# Thinkpad380ED.net
KiCad netlist of a schematic drawn in EAGLE
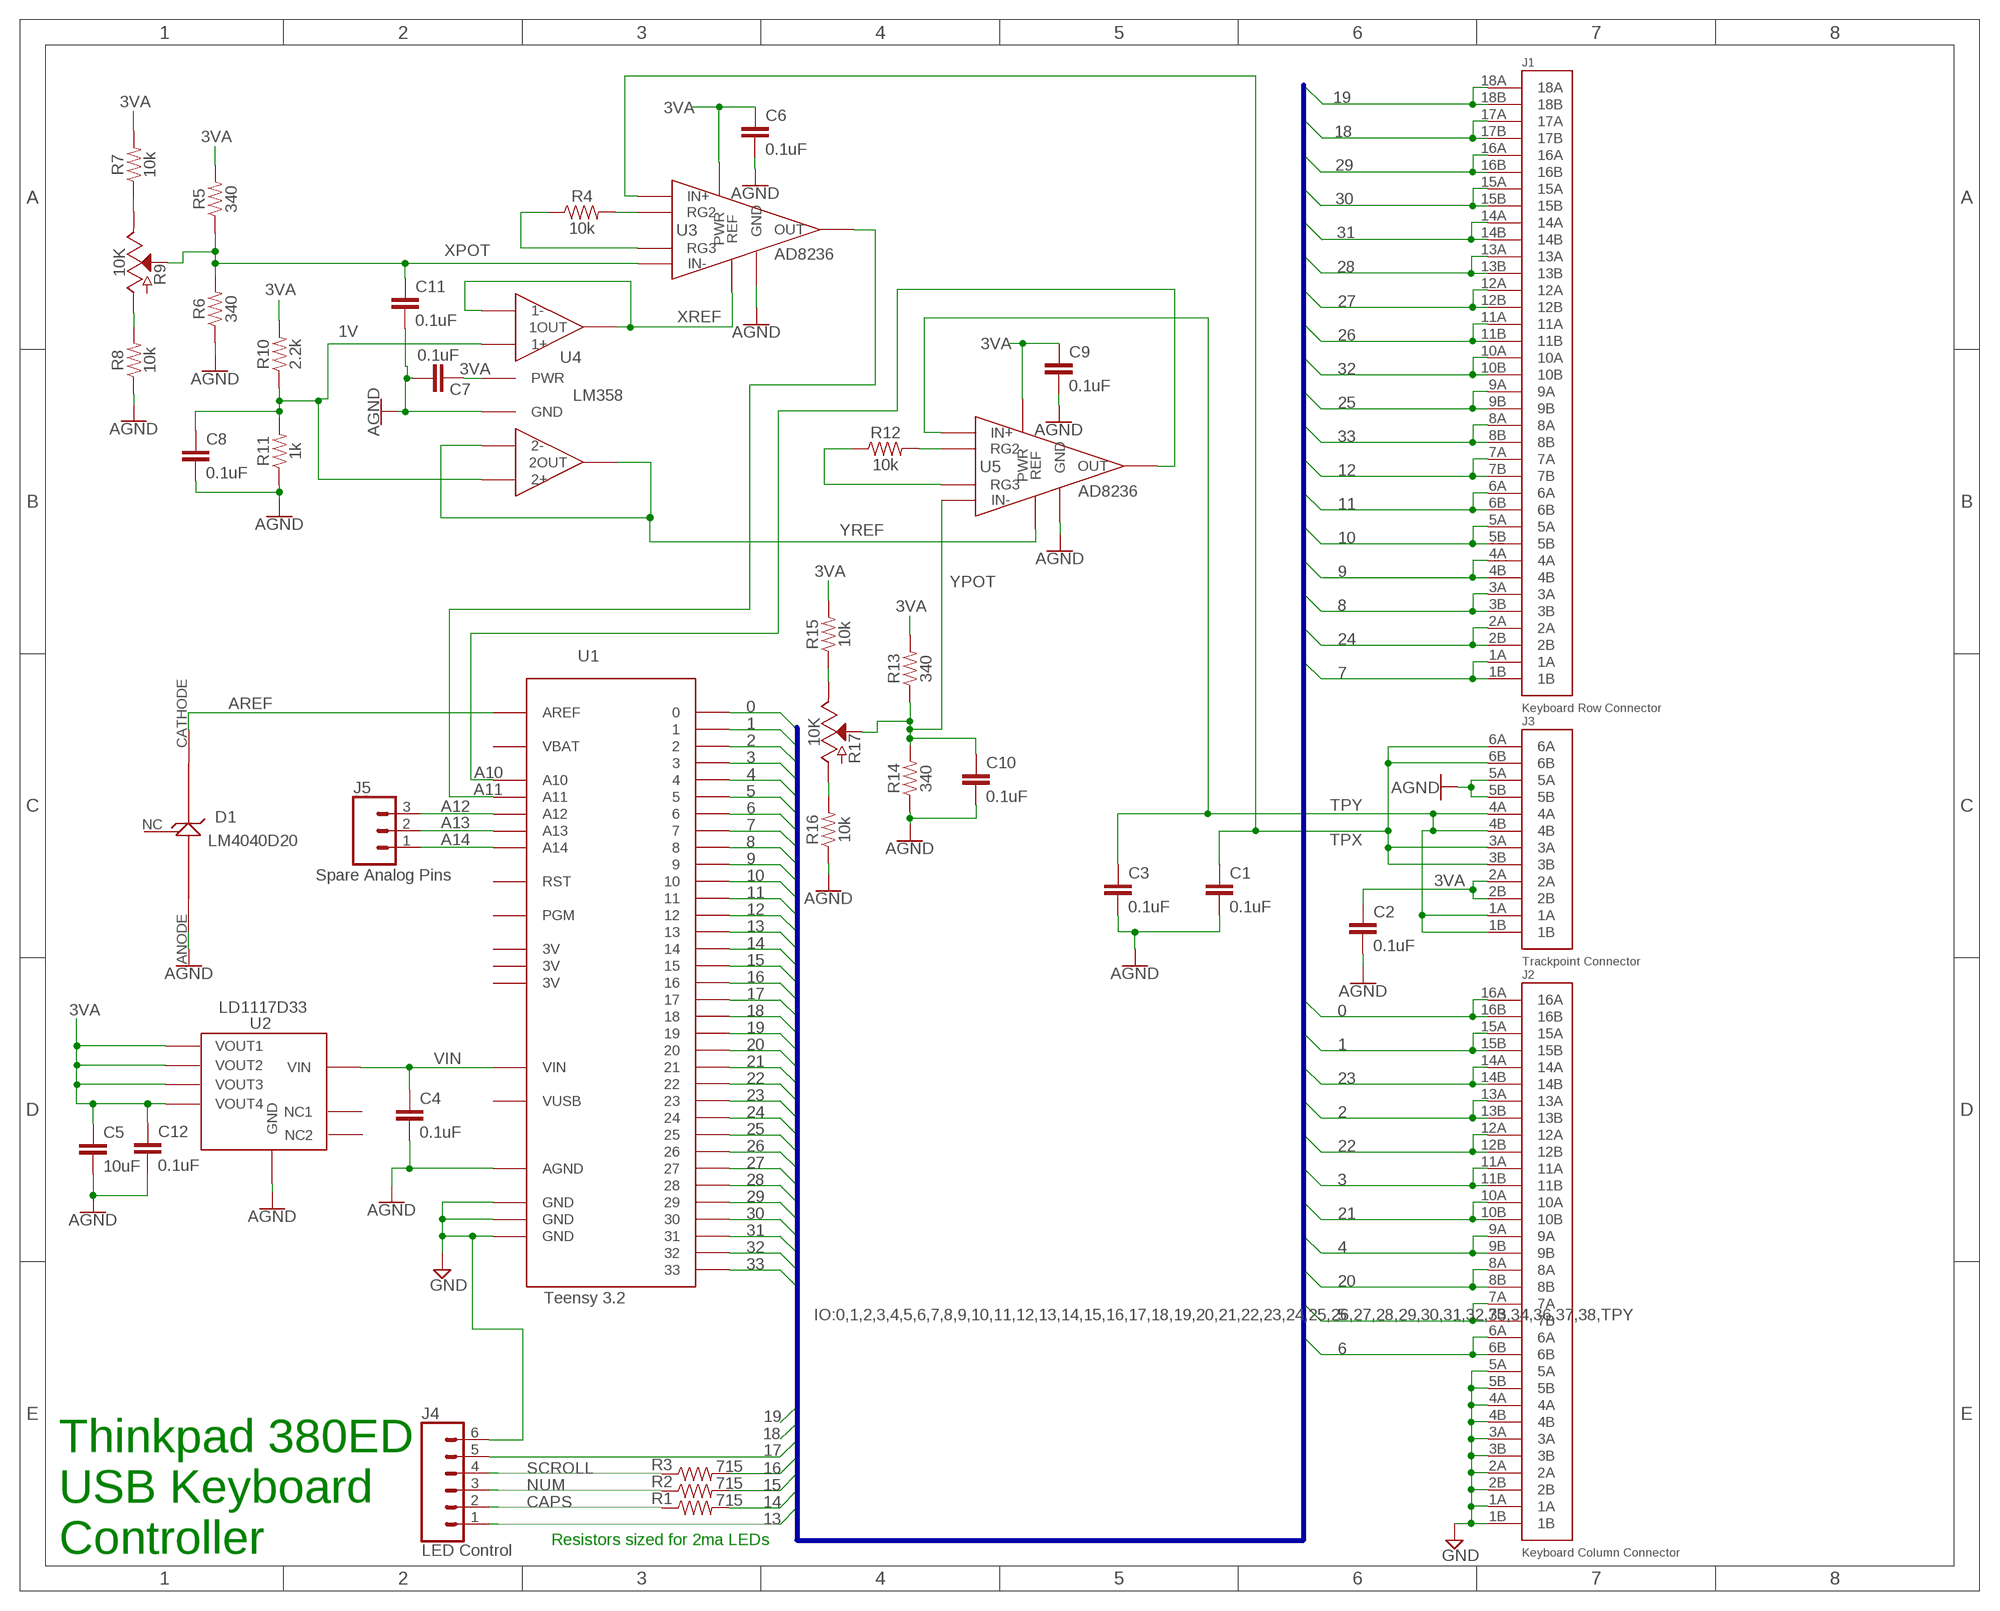
[diagram p0: schematic, sheet 1]

(export (version "E")
  (design (tool "Eeschema 10.0.6"))
  (components
    (comp (ref "C1")
      (value "0.1uF")
      (footprint "eagle-import:0603")
      (libsource (lib "eagle-import") (part "0.1UF-0603-25V-(+80/-20%)"))
    )
    (comp (ref "C2")
      (value "0.1uF")
      (footprint "eagle-import:0603")
      (libsource (lib "eagle-import") (part "0.1UF-0603-25V-(+80/-20%)"))
    )
    (comp (ref "C3")
      (value "0.1uF")
      (footprint "eagle-import:0603")
      (libsource (lib "eagle-import") (part "0.1UF-0603-25V-(+80/-20%)"))
    )
    (comp (ref "C4")
      (value "0.1uF")
      (footprint "eagle-import:0603")
      (libsource (lib "eagle-import") (part "0.1UF-0603-25V-(+80/-20%)"))
    )
    (comp (ref "C5")
      (value "10uF")
      (footprint "eagle-import:0603")
      (libsource (lib "eagle-import") (part "10UF-0603-6.3V-20%"))
    )
    (comp (ref "C6")
      (value "0.1uF")
      (footprint "eagle-import:0603")
      (libsource (lib "eagle-import") (part "0.1UF-0603-25V-(+80/-20%)"))
    )
    (comp (ref "C7")
      (value "0.1uF")
      (footprint "eagle-import:0603")
      (libsource (lib "eagle-import") (part "0.1UF-0603-25V-(+80/-20%)"))
    )
    (comp (ref "C8")
      (value "0.1uF")
      (footprint "eagle-import:0603")
      (libsource (lib "eagle-import") (part "0.1UF-0603-25V-(+80/-20%)"))
    )
    (comp (ref "C9")
      (value "0.1uF")
      (footprint "eagle-import:0603")
      (libsource (lib "eagle-import") (part "0.1UF-0603-25V-(+80/-20%)"))
    )
    (comp (ref "C10")
      (value "0.1uF")
      (footprint "eagle-import:0603")
      (libsource (lib "eagle-import") (part "0.1UF-0603-25V-(+80/-20%)"))
    )
    (comp (ref "C11")
      (value "0.1uF")
      (footprint "eagle-import:0603")
      (libsource (lib "eagle-import") (part "0.1UF-0603-25V-(+80/-20%)"))
    )
    (comp (ref "C12")
      (value "0.1uF")
      (footprint "eagle-import:0603")
      (libsource (lib "eagle-import") (part "0.1UF-0603-25V-(+80/-20%)"))
    )
    (comp (ref "D1")
      (value "LM4040D20")
      (footprint "eagle-import:LM4040")
      (libsource (lib "eagle-import") (part "LM4040"))
    )
    (comp (ref "J1")
      (value "Keyboard Row Connector")
      (footprint "eagle-import:0526101833")
      (libsource (lib "eagle-import") (part "0526101833"))
    )
    (comp (ref "J2")
      (value "Keyboard Column Connector")
      (footprint "eagle-import:0526101633")
      (libsource (lib "eagle-import") (part "0526101633"))
    )
    (comp (ref "J3")
      (value "Trackpoint Connector")
      (footprint "eagle-import:0526100633")
      (libsource (lib "eagle-import") (part "0526100633"))
    )
    (comp (ref "J4")
      (value "LED Control")
      (footprint "eagle-import:1X06")
      (libsource (lib "eagle-import") (part "CONN_06SILK_FEMALE_PTH"))
    )
    (comp (ref "J5")
      (value "Spare Analog Pins")
      (footprint "eagle-import:1X03")
      (libsource (lib "eagle-import") (part "CONN_03"))
    )
    (comp (ref "R1")
      (value "715")
      (footprint "eagle-import:0603")
      (libsource (lib "eagle-import") (part "715OHM-0603-1/10W-1%"))
    )
    (comp (ref "R2")
      (value "715")
      (footprint "eagle-import:0603")
      (libsource (lib "eagle-import") (part "715OHM-0603-1/10W-1%"))
    )
    (comp (ref "R3")
      (value "715")
      (footprint "eagle-import:0603")
      (libsource (lib "eagle-import") (part "715OHM-0603-1/10W-1%"))
    )
    (comp (ref "R4")
      (value "10k")
      (footprint "eagle-import:0603")
      (libsource (lib "eagle-import") (part "10KOHM-0603-1/10W-1%"))
    )
    (comp (ref "R5")
      (value "340")
      (footprint "eagle-import:0603")
      (libsource (lib "eagle-import") (part "340OHM-0603-1/10W-1%"))
    )
    (comp (ref "R6")
      (value "340")
      (footprint "eagle-import:0603")
      (libsource (lib "eagle-import") (part "340OHM-0603-1/10W-1%"))
    )
    (comp (ref "R7")
      (value "10k")
      (footprint "eagle-import:0603")
      (libsource (lib "eagle-import") (part "10KOHM-0603-1/10W-1%"))
    )
    (comp (ref "R8")
      (value "10k")
      (footprint "eagle-import:0603")
      (libsource (lib "eagle-import") (part "10KOHM-0603-1/10W-1%"))
    )
    (comp (ref "R9")
      (value "10K")
      (footprint "eagle-import:3296W-1-103LF")
      (libsource (lib "eagle-import") (part "3296W-1-103LF"))
    )
    (comp (ref "R10")
      (value "2.2k")
      (footprint "eagle-import:0603")
      (libsource (lib "eagle-import") (part "2.2KOHM-0603-1/10W-1%"))
    )
    (comp (ref "R11")
      (value "1k")
      (footprint "eagle-import:0603")
      (libsource (lib "eagle-import") (part "1KOHM-0603-1/10W-1%"))
    )
    (comp (ref "R12")
      (value "10k")
      (footprint "eagle-import:0603")
      (libsource (lib "eagle-import") (part "10KOHM-0603-1/10W-1%"))
    )
    (comp (ref "R13")
      (value "340")
      (footprint "eagle-import:0603")
      (libsource (lib "eagle-import") (part "340OHM-0603-1/10W-1%"))
    )
    (comp (ref "R14")
      (value "340")
      (footprint "eagle-import:0603")
      (libsource (lib "eagle-import") (part "340OHM-0603-1/10W-1%"))
    )
    (comp (ref "R15")
      (value "10k")
      (footprint "eagle-import:0603")
      (libsource (lib "eagle-import") (part "10KOHM-0603-1/10W-1%"))
    )
    (comp (ref "R16")
      (value "10k")
      (footprint "eagle-import:0603")
      (libsource (lib "eagle-import") (part "10KOHM-0603-1/10W-1%"))
    )
    (comp (ref "R17")
      (value "10K")
      (footprint "eagle-import:3296W-1-103LF")
      (libsource (lib "eagle-import") (part "3296W-1-103LF"))
    )
    (comp (ref "U1")
      (value "Teensy 3.2")
      (footprint "eagle-import:TEENSY_3P2")
      (libsource (lib "eagle-import") (part "TEENSY_3P2"))
    )
    (comp (ref "U2")
      (value "LD1117D33")
      (footprint "eagle-import:LD1117D33CTR")
      (libsource (lib "eagle-import") (part "LD1117D33CTR"))
    )
    (comp (ref "U3")
      (value "AD8236")
      (footprint "eagle-import:AD8236")
      (libsource (lib "eagle-import") (part "AD8236"))
    )
    (comp (ref "U4")
      (value "LM358")
      (footprint "eagle-import:LM358D")
      (libsource (lib "eagle-import") (part "LM358D"))
    )
    (comp (ref "U5")
      (value "AD8236")
      (footprint "eagle-import:AD8236")
      (libsource (lib "eagle-import") (part "AD8236"))
    )
  )
  (nets
    (net (code "6") (name "/0") (class "Default")
      (node (ref "J2") (pin "16A") (pinfunction "16A_16A") (pintype "bidirectional"))
      (node (ref "J2") (pin "16B") (pinfunction "16B_16B") (pintype "bidirectional"))
      (node (ref "U1") (pin "0") (pinfunction "0_0") (pintype "bidirectional"))
    )
    (net (code "7") (name "/1") (class "Default")
      (node (ref "J2") (pin "15A") (pinfunction "15A_15A") (pintype "bidirectional"))
      (node (ref "J2") (pin "15B") (pinfunction "15B_15B") (pintype "bidirectional"))
      (node (ref "U1") (pin "1") (pinfunction "1_1") (pintype "bidirectional"))
    )
    (net (code "8") (name "/1V") (class "Default")
      (node (ref "C8") (pin "1") (pinfunction "1_1") (pintype "passive"))
      (node (ref "R10") (pin "1") (pinfunction "1_1") (pintype "passive"))
      (node (ref "R11") (pin "2") (pinfunction "2_2") (pintype "passive"))
      (node (ref "U4") (pin "IN1+") (pinfunction "1+_IN1+") (pintype "bidirectional"))
      (node (ref "U4") (pin "IN2+") (pinfunction "2+_IN2+") (pintype "bidirectional"))
    )
    (net (code "9") (name "/2") (class "Default")
      (node (ref "J2") (pin "13A") (pinfunction "13A_13A") (pintype "bidirectional"))
      (node (ref "J2") (pin "13B") (pinfunction "13B_13B") (pintype "bidirectional"))
      (node (ref "U1") (pin "2") (pinfunction "2_2") (pintype "bidirectional"))
    )
    (net (code "10") (name "/3") (class "Default")
      (node (ref "J2") (pin "11A") (pinfunction "11A_11A") (pintype "bidirectional"))
      (node (ref "J2") (pin "11B") (pinfunction "11B_11B") (pintype "bidirectional"))
      (node (ref "U1") (pin "3") (pinfunction "3_3") (pintype "bidirectional"))
    )
    (net (code "11") (name "/3VA") (class "Default")
      (node (ref "C12") (pin "1") (pinfunction "1_1") (pintype "passive"))
      (node (ref "C2") (pin "1") (pinfunction "1_1") (pintype "passive"))
      (node (ref "C5") (pin "1") (pinfunction "1_1") (pintype "passive"))
      (node (ref "C6") (pin "1") (pinfunction "1_1") (pintype "passive"))
      (node (ref "C7") (pin "1") (pinfunction "1_1") (pintype "passive"))
      (node (ref "C9") (pin "1") (pinfunction "1_1") (pintype "passive"))
      (node (ref "J3") (pin "2A") (pinfunction "2A_2A") (pintype "bidirectional"))
      (node (ref "J3") (pin "2B") (pinfunction "2B_2B") (pintype "bidirectional"))
      (node (ref "R10") (pin "2") (pinfunction "2_2") (pintype "passive"))
      (node (ref "R13") (pin "2") (pinfunction "2_2") (pintype "passive"))
      (node (ref "R15") (pin "2") (pinfunction "2_2") (pintype "passive"))
      (node (ref "R5") (pin "2") (pinfunction "2_2") (pintype "passive"))
      (node (ref "R7") (pin "2") (pinfunction "2_2") (pintype "passive"))
      (node (ref "U2") (pin "VOUT1") (pinfunction "VOUT1_VOUT1") (pintype "bidirectional"))
      (node (ref "U2") (pin "VOUT2") (pinfunction "VOUT2_VOUT2") (pintype "bidirectional"))
      (node (ref "U2") (pin "VOUT3") (pinfunction "VOUT3_VOUT3") (pintype "bidirectional"))
      (node (ref "U2") (pin "VOUT4") (pinfunction "VOUT4_VOUT4") (pintype "bidirectional"))
      (node (ref "U3") (pin "PWR") (pinfunction "PWR_PWR") (pintype "bidirectional"))
      (node (ref "U4") (pin "PWR") (pinfunction "PWR_PWR") (pintype "bidirectional"))
      (node (ref "U5") (pin "PWR") (pinfunction "PWR_PWR") (pintype "bidirectional"))
    )
    (net (code "12") (name "/4") (class "Default")
      (node (ref "J2") (pin "9A") (pinfunction "9A_9A") (pintype "bidirectional"))
      (node (ref "J2") (pin "9B") (pinfunction "9B_9B") (pintype "bidirectional"))
      (node (ref "U1") (pin "4") (pinfunction "4_4") (pintype "bidirectional"))
    )
    (net (code "13") (name "/5") (class "Default")
      (node (ref "J2") (pin "7A") (pinfunction "7A_7A") (pintype "bidirectional"))
      (node (ref "J2") (pin "7B") (pinfunction "7B_7B") (pintype "bidirectional"))
      (node (ref "U1") (pin "5") (pinfunction "5_5") (pintype "bidirectional"))
    )
    (net (code "14") (name "/6") (class "Default")
      (node (ref "J2") (pin "6A") (pinfunction "6A_6A") (pintype "bidirectional"))
      (node (ref "J2") (pin "6B") (pinfunction "6B_6B") (pintype "bidirectional"))
      (node (ref "U1") (pin "6") (pinfunction "6_6") (pintype "bidirectional"))
    )
    (net (code "15") (name "/7") (class "Default")
      (node (ref "J1") (pin "1A") (pinfunction "1A_1A") (pintype "bidirectional"))
      (node (ref "J1") (pin "1B") (pinfunction "1B_1B") (pintype "bidirectional"))
      (node (ref "U1") (pin "7") (pinfunction "7_7") (pintype "bidirectional"))
    )
    (net (code "16") (name "/8") (class "Default")
      (node (ref "J1") (pin "3A") (pinfunction "3A_3A") (pintype "bidirectional"))
      (node (ref "J1") (pin "3B") (pinfunction "3B_3B") (pintype "bidirectional"))
      (node (ref "U1") (pin "8") (pinfunction "8_8") (pintype "bidirectional"))
    )
    (net (code "17") (name "/9") (class "Default")
      (node (ref "J1") (pin "4A") (pinfunction "4A_4A") (pintype "bidirectional"))
      (node (ref "J1") (pin "4B") (pinfunction "4B_4B") (pintype "bidirectional"))
      (node (ref "U1") (pin "9") (pinfunction "9_9") (pintype "bidirectional"))
    )
    (net (code "18") (name "/10") (class "Default")
      (node (ref "J1") (pin "5A") (pinfunction "5A_5A") (pintype "bidirectional"))
      (node (ref "J1") (pin "5B") (pinfunction "5B_5B") (pintype "bidirectional"))
      (node (ref "U1") (pin "10") (pinfunction "10_10") (pintype "bidirectional"))
    )
    (net (code "19") (name "/11") (class "Default")
      (node (ref "J1") (pin "6A") (pinfunction "6A_6A") (pintype "bidirectional"))
      (node (ref "J1") (pin "6B") (pinfunction "6B_6B") (pintype "bidirectional"))
      (node (ref "U1") (pin "11") (pinfunction "11_11") (pintype "bidirectional"))
    )
    (net (code "20") (name "/12") (class "Default")
      (node (ref "J1") (pin "7A") (pinfunction "7A_7A") (pintype "bidirectional"))
      (node (ref "J1") (pin "7B") (pinfunction "7B_7B") (pintype "bidirectional"))
      (node (ref "U1") (pin "12") (pinfunction "12_12") (pintype "bidirectional"))
    )
    (net (code "21") (name "/13") (class "Default")
      (node (ref "J4") (pin "1") (pinfunction "1_1") (pintype "passive"))
      (node (ref "U1") (pin "13") (pinfunction "13_13") (pintype "bidirectional"))
    )
    (net (code "22") (name "/14") (class "Default")
      (node (ref "R1") (pin "2") (pinfunction "2_2") (pintype "passive"))
      (node (ref "U1") (pin "14") (pinfunction "14_14") (pintype "bidirectional"))
    )
    (net (code "23") (name "/15") (class "Default")
      (node (ref "R2") (pin "2") (pinfunction "2_2") (pintype "passive"))
      (node (ref "U1") (pin "15") (pinfunction "15_15") (pintype "bidirectional"))
    )
    (net (code "24") (name "/16") (class "Default")
      (node (ref "R3") (pin "2") (pinfunction "2_2") (pintype "passive"))
      (node (ref "U1") (pin "16") (pinfunction "16_16") (pintype "bidirectional"))
    )
    (net (code "25") (name "/17") (class "Default")
      (node (ref "J4") (pin "5") (pinfunction "5_5") (pintype "passive"))
      (node (ref "U1") (pin "17") (pinfunction "17_17") (pintype "bidirectional"))
    )
    (net (code "26") (name "/18") (class "Default")
      (node (ref "J1") (pin "17A") (pinfunction "17A_17A") (pintype "bidirectional"))
      (node (ref "J1") (pin "17B") (pinfunction "17B_17B") (pintype "bidirectional"))
      (node (ref "U1") (pin "18") (pinfunction "18_18") (pintype "bidirectional"))
    )
    (net (code "27") (name "/19") (class "Default")
      (node (ref "J1") (pin "18A") (pinfunction "18A_18A") (pintype "bidirectional"))
      (node (ref "J1") (pin "18B") (pinfunction "18B_18B") (pintype "bidirectional"))
      (node (ref "U1") (pin "19") (pinfunction "19_19") (pintype "bidirectional"))
    )
    (net (code "28") (name "/20") (class "Default")
      (node (ref "J2") (pin "8A") (pinfunction "8A_8A") (pintype "bidirectional"))
      (node (ref "J2") (pin "8B") (pinfunction "8B_8B") (pintype "bidirectional"))
      (node (ref "U1") (pin "20") (pinfunction "20_20") (pintype "bidirectional"))
    )
    (net (code "29") (name "/21") (class "Default")
      (node (ref "J2") (pin "10A") (pinfunction "10A_10A") (pintype "bidirectional"))
      (node (ref "J2") (pin "10B") (pinfunction "10B_10B") (pintype "bidirectional"))
      (node (ref "U1") (pin "21") (pinfunction "21_21") (pintype "bidirectional"))
    )
    (net (code "30") (name "/22") (class "Default")
      (node (ref "J2") (pin "12A") (pinfunction "12A_12A") (pintype "bidirectional"))
      (node (ref "J2") (pin "12B") (pinfunction "12B_12B") (pintype "bidirectional"))
      (node (ref "U1") (pin "22") (pinfunction "22_22") (pintype "bidirectional"))
    )
    (net (code "31") (name "/23") (class "Default")
      (node (ref "J2") (pin "14A") (pinfunction "14A_14A") (pintype "bidirectional"))
      (node (ref "J2") (pin "14B") (pinfunction "14B_14B") (pintype "bidirectional"))
      (node (ref "U1") (pin "23") (pinfunction "23_23") (pintype "bidirectional"))
    )
    (net (code "32") (name "/24") (class "Default")
      (node (ref "J1") (pin "2A") (pinfunction "2A_2A") (pintype "bidirectional"))
      (node (ref "J1") (pin "2B") (pinfunction "2B_2B") (pintype "bidirectional"))
      (node (ref "U1") (pin "24") (pinfunction "24_24") (pintype "bidirectional"))
    )
    (net (code "33") (name "/25") (class "Default")
      (node (ref "J1") (pin "9A") (pinfunction "9A_9A") (pintype "bidirectional"))
      (node (ref "J1") (pin "9B") (pinfunction "9B_9B") (pintype "bidirectional"))
      (node (ref "U1") (pin "25") (pinfunction "25_25") (pintype "bidirectional"))
    )
    (net (code "34") (name "/26") (class "Default")
      (node (ref "J1") (pin "11A") (pinfunction "11A_11A") (pintype "bidirectional"))
      (node (ref "J1") (pin "11B") (pinfunction "11B_11B") (pintype "bidirectional"))
      (node (ref "U1") (pin "26") (pinfunction "26_26") (pintype "bidirectional"))
    )
    (net (code "35") (name "/27") (class "Default")
      (node (ref "J1") (pin "12A") (pinfunction "12A_12A") (pintype "bidirectional"))
      (node (ref "J1") (pin "12B") (pinfunction "12B_12B") (pintype "bidirectional"))
      (node (ref "U1") (pin "27") (pinfunction "27_27") (pintype "bidirectional"))
    )
    (net (code "36") (name "/28") (class "Default")
      (node (ref "J1") (pin "13A") (pinfunction "13A_13A") (pintype "bidirectional"))
      (node (ref "J1") (pin "13B") (pinfunction "13B_13B") (pintype "bidirectional"))
      (node (ref "U1") (pin "28") (pinfunction "28_28") (pintype "bidirectional"))
    )
    (net (code "37") (name "/29") (class "Default")
      (node (ref "J1") (pin "16A") (pinfunction "16A_16A") (pintype "bidirectional"))
      (node (ref "J1") (pin "16B") (pinfunction "16B_16B") (pintype "bidirectional"))
      (node (ref "U1") (pin "29") (pinfunction "29_29") (pintype "bidirectional"))
    )
    (net (code "38") (name "/30") (class "Default")
      (node (ref "J1") (pin "15A") (pinfunction "15A_15A") (pintype "bidirectional"))
      (node (ref "J1") (pin "15B") (pinfunction "15B_15B") (pintype "bidirectional"))
      (node (ref "U1") (pin "30") (pinfunction "30_30") (pintype "bidirectional"))
    )
    (net (code "39") (name "/31") (class "Default")
      (node (ref "J1") (pin "14A") (pinfunction "14A_14A") (pintype "bidirectional"))
      (node (ref "J1") (pin "14B") (pinfunction "14B_14B") (pintype "bidirectional"))
      (node (ref "U1") (pin "31") (pinfunction "31_31") (pintype "bidirectional"))
    )
    (net (code "40") (name "/32") (class "Default")
      (node (ref "J1") (pin "10A") (pinfunction "10A_10A") (pintype "bidirectional"))
      (node (ref "J1") (pin "10B") (pinfunction "10B_10B") (pintype "bidirectional"))
      (node (ref "U1") (pin "32") (pinfunction "32_32") (pintype "bidirectional"))
    )
    (net (code "41") (name "/33") (class "Default")
      (node (ref "J1") (pin "8A") (pinfunction "8A_8A") (pintype "bidirectional"))
      (node (ref "J1") (pin "8B") (pinfunction "8B_8B") (pintype "bidirectional"))
      (node (ref "U1") (pin "33") (pinfunction "33_33") (pintype "bidirectional"))
    )
    (net (code "42") (name "/A10") (class "Default")
      (node (ref "U1") (pin "A10") (pinfunction "A10_A10") (pintype "bidirectional"))
      (node (ref "U5") (pin "VOUT") (pinfunction "OUT_VOUT") (pintype "bidirectional"))
    )
    (net (code "43") (name "/A11") (class "Default")
      (node (ref "U1") (pin "A11") (pinfunction "A11_A11") (pintype "bidirectional"))
      (node (ref "U3") (pin "VOUT") (pinfunction "OUT_VOUT") (pintype "bidirectional"))
    )
    (net (code "44") (name "/A12") (class "Default")
      (node (ref "J5") (pin "3") (pinfunction "3_3") (pintype "passive"))
      (node (ref "U1") (pin "A12") (pinfunction "A12_A12") (pintype "bidirectional"))
    )
    (net (code "45") (name "/A13") (class "Default")
      (node (ref "J5") (pin "2") (pinfunction "2_2") (pintype "passive"))
      (node (ref "U1") (pin "A13") (pinfunction "A13_A13") (pintype "bidirectional"))
    )
    (net (code "46") (name "/A14") (class "Default")
      (node (ref "J5") (pin "1") (pinfunction "1_1") (pintype "passive"))
      (node (ref "U1") (pin "A14") (pinfunction "A14_A14") (pintype "bidirectional"))
    )
    (net (code "47") (name "/AREF") (class "Default")
      (node (ref "D1") (pin "CATHODE") (pinfunction "CATHODE_CATHODE") (pintype "bidirectional"))
      (node (ref "U1") (pin "AREF") (pinfunction "AREF_AREF") (pintype "bidirectional"))
    )
    (net (code "48") (name "/CAPS") (class "Default")
      (node (ref "J4") (pin "2") (pinfunction "2_2") (pintype "passive"))
      (node (ref "R1") (pin "1") (pinfunction "1_1") (pintype "passive"))
    )
    (net (code "49") (name "/NUM") (class "Default")
      (node (ref "J4") (pin "3") (pinfunction "3_3") (pintype "passive"))
      (node (ref "R2") (pin "1") (pinfunction "1_1") (pintype "passive"))
    )
    (net (code "50") (name "/SCROLL") (class "Default")
      (node (ref "J4") (pin "4") (pinfunction "4_4") (pintype "passive"))
      (node (ref "R3") (pin "1") (pinfunction "1_1") (pintype "passive"))
    )
    (net (code "51") (name "/TPX") (class "Default")
      (node (ref "C1") (pin "1") (pinfunction "1_1") (pintype "passive"))
      (node (ref "J3") (pin "3A") (pinfunction "3A_3A") (pintype "bidirectional"))
      (node (ref "J3") (pin "3B") (pinfunction "3B_3B") (pintype "bidirectional"))
      (node (ref "J3") (pin "6A") (pinfunction "6A_6A") (pintype "bidirectional"))
      (node (ref "J3") (pin "6B") (pinfunction "6B_6B") (pintype "bidirectional"))
      (node (ref "U3") (pin "IN+") (pinfunction "IN+_IN+") (pintype "bidirectional"))
    )
    (net (code "52") (name "/TPY") (class "Default")
      (node (ref "C3") (pin "1") (pinfunction "1_1") (pintype "passive"))
      (node (ref "J3") (pin "1A") (pinfunction "1A_1A") (pintype "bidirectional"))
      (node (ref "J3") (pin "1B") (pinfunction "1B_1B") (pintype "bidirectional"))
      (node (ref "J3") (pin "4A") (pinfunction "4A_4A") (pintype "bidirectional"))
      (node (ref "J3") (pin "4B") (pinfunction "4B_4B") (pintype "bidirectional"))
      (node (ref "U5") (pin "IN+") (pinfunction "IN+_IN+") (pintype "bidirectional"))
    )
    (net (code "53") (name "/VIN") (class "Default")
      (node (ref "C4") (pin "1") (pinfunction "1_1") (pintype "passive"))
      (node (ref "U1") (pin "VIN") (pinfunction "VIN_VIN") (pintype "bidirectional"))
      (node (ref "U2") (pin "VIN") (pinfunction "VIN_VIN") (pintype "bidirectional"))
    )
    (net (code "54") (name "/XPOT") (class "Default")
      (node (ref "C11") (pin "1") (pinfunction "1_1") (pintype "passive"))
      (node (ref "R5") (pin "1") (pinfunction "1_1") (pintype "passive"))
      (node (ref "R6") (pin "2") (pinfunction "2_2") (pintype "passive"))
      (node (ref "R9") (pin "S") (pinfunction "S_S") (pintype "passive"))
      (node (ref "U3") (pin "IN-") (pinfunction "IN-_IN-") (pintype "bidirectional"))
    )
    (net (code "55") (name "/XREF") (class "Default")
      (node (ref "U3") (pin "REF") (pinfunction "REF_REF") (pintype "bidirectional"))
      (node (ref "U4") (pin "IN1-") (pinfunction "1-_IN1-") (pintype "bidirectional"))
      (node (ref "U4") (pin "OUT1") (pinfunction "1OUT_OUT1") (pintype "bidirectional"))
    )
    (net (code "56") (name "/YPOT") (class "Default")
      (node (ref "C10") (pin "1") (pinfunction "1_1") (pintype "passive"))
      (node (ref "R13") (pin "1") (pinfunction "1_1") (pintype "passive"))
      (node (ref "R14") (pin "2") (pinfunction "2_2") (pintype "passive"))
      (node (ref "R17") (pin "S") (pinfunction "S_S") (pintype "passive"))
      (node (ref "U5") (pin "IN-") (pinfunction "IN-_IN-") (pintype "bidirectional"))
    )
    (net (code "57") (name "/YREF") (class "Default")
      (node (ref "U4") (pin "IN2-") (pinfunction "2-_IN2-") (pintype "bidirectional"))
      (node (ref "U4") (pin "OUT2") (pinfunction "2OUT_OUT2") (pintype "bidirectional"))
      (node (ref "U5") (pin "REF") (pinfunction "REF_REF") (pintype "bidirectional"))
    )
    (net (code "59") (name "AGND") (class "Default")
      (node (ref "C1") (pin "2") (pinfunction "2_2") (pintype "passive"))
      (node (ref "C10") (pin "2") (pinfunction "2_2") (pintype "passive"))
      (node (ref "C11") (pin "2") (pinfunction "2_2") (pintype "passive"))
      (node (ref "C12") (pin "2") (pinfunction "2_2") (pintype "passive"))
      (node (ref "C2") (pin "2") (pinfunction "2_2") (pintype "passive"))
      (node (ref "C3") (pin "2") (pinfunction "2_2") (pintype "passive"))
      (node (ref "C4") (pin "2") (pinfunction "2_2") (pintype "passive"))
      (node (ref "C5") (pin "2") (pinfunction "2_2") (pintype "passive"))
      (node (ref "C6") (pin "2") (pinfunction "2_2") (pintype "passive"))
      (node (ref "C7") (pin "2") (pinfunction "2_2") (pintype "passive"))
      (node (ref "C8") (pin "2") (pinfunction "2_2") (pintype "passive"))
      (node (ref "C9") (pin "2") (pinfunction "2_2") (pintype "passive"))
      (node (ref "D1") (pin "ANODE") (pinfunction "ANODE_ANODE") (pintype "bidirectional"))
      (node (ref "J3") (pin "5A") (pinfunction "5A_5A") (pintype "bidirectional"))
      (node (ref "J3") (pin "5B") (pinfunction "5B_5B") (pintype "bidirectional"))
      (node (ref "R11") (pin "1") (pinfunction "1_1") (pintype "passive"))
      (node (ref "R14") (pin "1") (pinfunction "1_1") (pintype "passive"))
      (node (ref "R16") (pin "1") (pinfunction "1_1") (pintype "passive"))
      (node (ref "R6") (pin "1") (pinfunction "1_1") (pintype "passive"))
      (node (ref "R8") (pin "1") (pinfunction "1_1") (pintype "passive"))
      (node (ref "U1") (pin "AGND") (pinfunction "AGND_AGND") (pintype "bidirectional"))
      (node (ref "U2") (pin "GND") (pinfunction "GND_GND") (pintype "bidirectional"))
      (node (ref "U3") (pin "GND") (pinfunction "GND_GND") (pintype "bidirectional"))
      (node (ref "U4") (pin "GND") (pinfunction "GND_GND") (pintype "bidirectional"))
      (node (ref "U5") (pin "GND") (pinfunction "GND_GND") (pintype "bidirectional"))
    )
    (net (code "60") (name "GND") (class "Default")
      (node (ref "J2") (pin "1A") (pinfunction "1A_1A") (pintype "bidirectional"))
      (node (ref "J2") (pin "1B") (pinfunction "1B_1B") (pintype "bidirectional"))
      (node (ref "J2") (pin "2A") (pinfunction "2A_2A") (pintype "bidirectional"))
      (node (ref "J2") (pin "2B") (pinfunction "2B_2B") (pintype "bidirectional"))
      (node (ref "J2") (pin "3A") (pinfunction "3A_3A") (pintype "bidirectional"))
      (node (ref "J2") (pin "3B") (pinfunction "3B_3B") (pintype "bidirectional"))
      (node (ref "J2") (pin "4A") (pinfunction "4A_4A") (pintype "bidirectional"))
      (node (ref "J2") (pin "4B") (pinfunction "4B_4B") (pintype "bidirectional"))
      (node (ref "J2") (pin "5A") (pinfunction "5A_5A") (pintype "bidirectional"))
      (node (ref "J2") (pin "5B") (pinfunction "5B_5B") (pintype "bidirectional"))
      (node (ref "J4") (pin "6") (pinfunction "6_6") (pintype "passive"))
      (node (ref "U1") (pin "GND1") (pinfunction "GND_GND1") (pintype "bidirectional"))
      (node (ref "U1") (pin "GND2") (pinfunction "GND_GND2") (pintype "bidirectional"))
      (node (ref "U1") (pin "GND3") (pinfunction "GND_GND3") (pintype "bidirectional"))
    )
    (net (code "61") (name "Net-(R4-Pad1)") (class "Default")
      (node (ref "R4") (pin "1") (pinfunction "1_1") (pintype "passive"))
      (node (ref "U3") (pin "RG3") (pinfunction "RG3_RG3") (pintype "bidirectional"))
    )
    (net (code "62") (name "Net-(R4-Pad2)") (class "Default")
      (node (ref "R4") (pin "2") (pinfunction "2_2") (pintype "passive"))
      (node (ref "U3") (pin "RG2") (pinfunction "RG2_RG2") (pintype "bidirectional"))
    )
    (net (code "63") (name "Net-(R7-Pad1)") (class "Default")
      (node (ref "R7") (pin "1") (pinfunction "1_1") (pintype "passive"))
      (node (ref "R9") (pin "E") (pinfunction "E_E") (pintype "passive"))
    )
    (net (code "64") (name "Net-(R8-Pad2)") (class "Default")
      (node (ref "R8") (pin "2") (pinfunction "2_2") (pintype "passive"))
      (node (ref "R9") (pin "A") (pinfunction "A_A") (pintype "passive"))
    )
    (net (code "65") (name "Net-(R12-Pad1)") (class "Default")
      (node (ref "R12") (pin "1") (pinfunction "1_1") (pintype "passive"))
      (node (ref "U5") (pin "RG3") (pinfunction "RG3_RG3") (pintype "bidirectional"))
    )
    (net (code "66") (name "Net-(R12-Pad2)") (class "Default")
      (node (ref "R12") (pin "2") (pinfunction "2_2") (pintype "passive"))
      (node (ref "U5") (pin "RG2") (pinfunction "RG2_RG2") (pintype "bidirectional"))
    )
    (net (code "67") (name "Net-(R15-Pad1)") (class "Default")
      (node (ref "R15") (pin "1") (pinfunction "1_1") (pintype "passive"))
      (node (ref "R17") (pin "E") (pinfunction "E_E") (pintype "passive"))
    )
    (net (code "68") (name "Net-(R16-Pad2)") (class "Default")
      (node (ref "R16") (pin "2") (pinfunction "2_2") (pintype "passive"))
      (node (ref "R17") (pin "A") (pinfunction "A_A") (pintype "passive"))
    )
    (net (code "69") (name "unconnected-(D1-PadNC)") (class "Default")
      (node (ref "D1") (pin "NC") (pinfunction "NC_NC") (pintype "bidirectional"))
    )
    (net (code "70") (name "unconnected-(U1-3V-Pad3V1)") (class "Default")
      (node (ref "U1") (pin "3V1") (pinfunction "3V_3V1") (pintype "bidirectional"))
    )
    (net (code "71") (name "unconnected-(U1-3V-Pad3V2)") (class "Default")
      (node (ref "U1") (pin "3V2") (pinfunction "3V_3V2") (pintype "bidirectional"))
    )
    (net (code "72") (name "unconnected-(U1-3V-Pad3V3)") (class "Default")
      (node (ref "U1") (pin "3V3") (pinfunction "3V_3V3") (pintype "bidirectional"))
    )
    (net (code "73") (name "unconnected-(U1-PadPGM)") (class "Default")
      (node (ref "U1") (pin "PGM") (pinfunction "PGM_PGM") (pintype "bidirectional"))
    )
    (net (code "74") (name "unconnected-(U1-PadRST)") (class "Default")
      (node (ref "U1") (pin "RST") (pinfunction "RST_RST") (pintype "bidirectional"))
    )
    (net (code "75") (name "unconnected-(U1-PadVBAT)") (class "Default")
      (node (ref "U1") (pin "VBAT") (pinfunction "VBAT_VBAT") (pintype "bidirectional"))
    )
    (net (code "76") (name "unconnected-(U1-PadVUSB)") (class "Default")
      (node (ref "U1") (pin "VUSB") (pinfunction "VUSB_VUSB") (pintype "bidirectional"))
    )
    (net (code "77") (name "unconnected-(U2-PadNC1)") (class "Default")
      (node (ref "U2") (pin "NC1") (pinfunction "NC1_NC1") (pintype "bidirectional"))
    )
    (net (code "78") (name "unconnected-(U2-PadNC2)") (class "Default")
      (node (ref "U2") (pin "NC2") (pinfunction "NC2_NC2") (pintype "bidirectional"))
    )
  )
)
